# Sheet1.net
KiCad netlist of a schematic drawn in Altium Designer
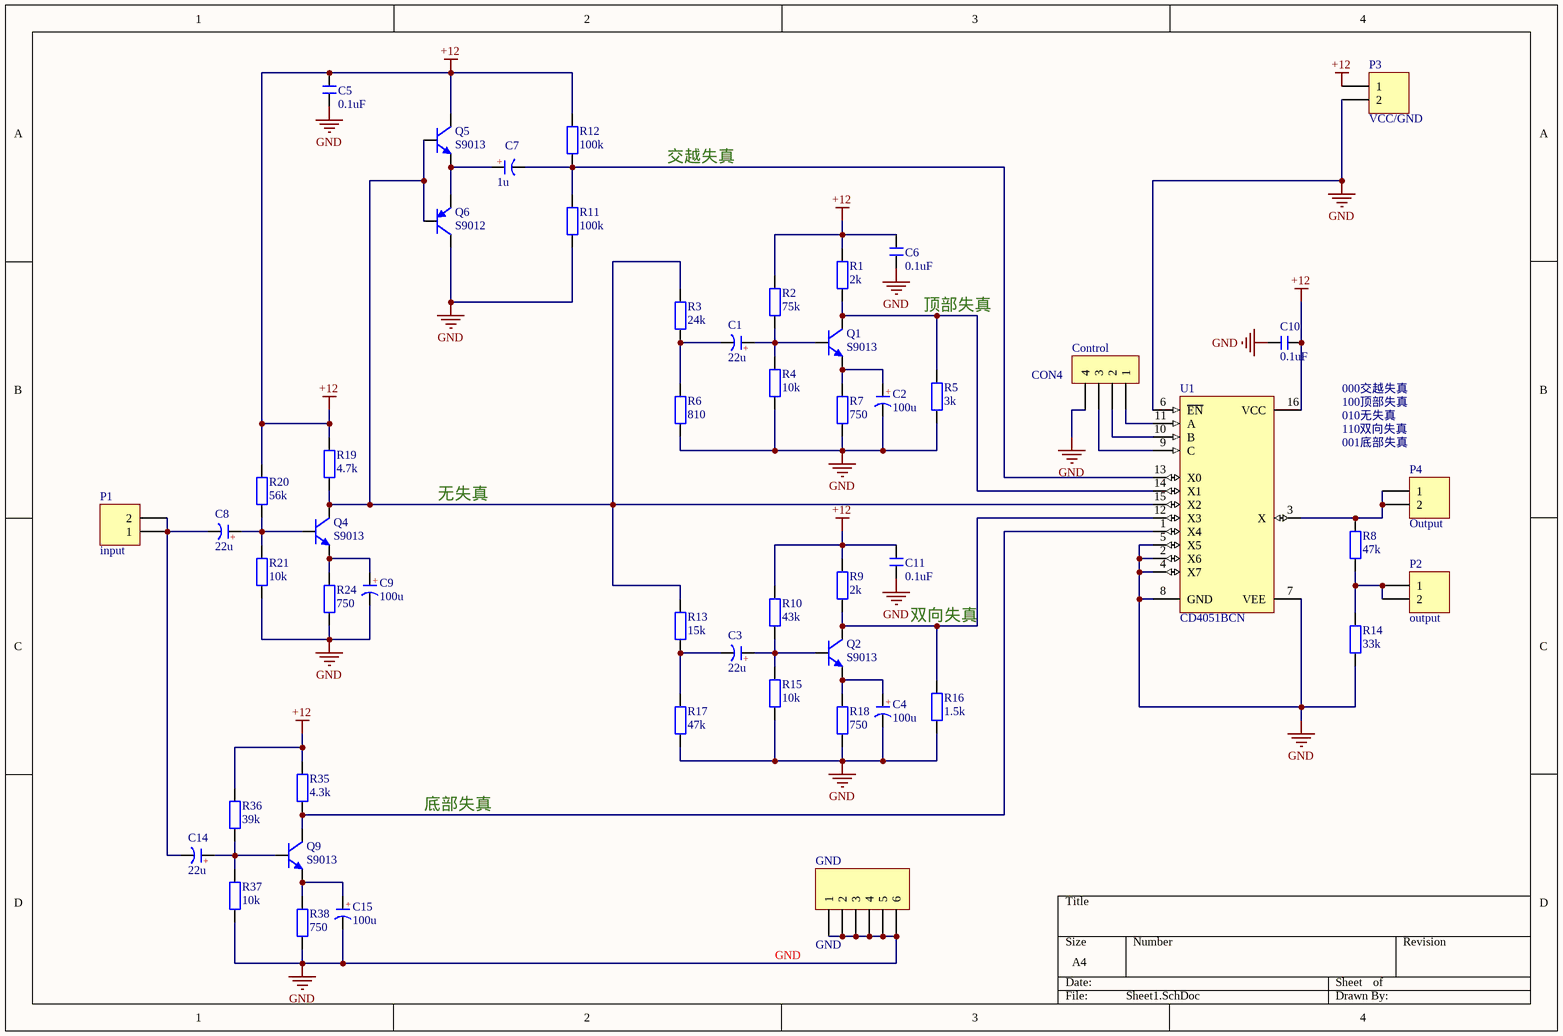
[diagram p0: Sheet1.SchDoc]

(export (version "E")
  (design (tool "Eeschema 10.0.6"))
  (components
    (comp (ref "C1")
      (value "22u")
      (footprint "CS 3.5*8*8 - R")
      (description "直插固态电容")
      (fields (field (name "版权归属") "源创客"))
      (libsource (lib "") (part "C-CS_1"))
    )
    (comp (ref "C2")
      (value "100u")
      (footprint "CS 3.5*8*8 - R")
      (description "直插固态电容")
      (fields (field (name "版权归属") "源创客"))
      (libsource (lib "3.1   - 电阻-电容-电感") (part "C-CS"))
    )
    (comp (ref "C3")
      (value "22u")
      (footprint "CS 3.5*8*8 - R")
      (description "直插固态电容")
      (fields (field (name "版权归属") "源创客"))
      (libsource (lib "") (part "C-CS_1"))
    )
    (comp (ref "C4")
      (value "100u")
      (footprint "CS 3.5*8*8 - R")
      (description "直插固态电容")
      (fields (field (name "版权归属") "源创客"))
      (libsource (lib "3.1   - 电阻-电容-电感") (part "C-CS"))
    )
    (comp (ref "C5")
      (value "0.1uF")
      (footprint "CBB-CL71")
      (description "CBB电容")
      (fields (field (name "版权归属") "源创客"))
      (libsource (lib "3.1   - 电阻-电容-电感") (part "C-CBB"))
    )
    (comp (ref "C6")
      (value "0.1uF")
      (footprint "CBB-CL71")
      (description "CBB电容")
      (fields (field (name "版权归属") "源创客"))
      (libsource (lib "3.1   - 电阻-电容-电感") (part "C-CBB"))
    )
    (comp (ref "C7")
      (value "1u")
      (footprint "CS 3.5*8*8 - R")
      (description "直插固态电容")
      (fields (field (name "版权归属") "源创客"))
      (libsource (lib "") (part "C-CS_1"))
    )
    (comp (ref "C8")
      (value "22u")
      (footprint "CS 3.5*8*8 - R")
      (description "直插固态电容")
      (fields (field (name "版权归属") "源创客"))
      (libsource (lib "") (part "C-CS_1"))
    )
    (comp (ref "C9")
      (value "100u")
      (footprint "CS 3.5*8*8 - R")
      (description "直插固态电容")
      (fields (field (name "版权归属") "源创客"))
      (libsource (lib "3.1   - 电阻-电容-电感") (part "C-CS"))
    )
    (comp (ref "C10")
      (value "0.1uF")
      (footprint "CBB-CL71")
      (description "CBB电容")
      (fields (field (name "版权归属") "源创客"))
      (libsource (lib "3.1   - 电阻-电容-电感") (part "C-CBB"))
    )
    (comp (ref "C11")
      (value "0.1uF")
      (footprint "CBB-CL71")
      (description "CBB电容")
      (fields (field (name "版权归属") "源创客"))
      (libsource (lib "3.1   - 电阻-电容-电感") (part "C-CBB"))
    )
    (comp (ref "C14")
      (value "22u")
      (footprint "CS 3.5*8*8 - R")
      (description "直插固态电容")
      (fields (field (name "版权归属") "源创客"))
      (libsource (lib "") (part "C-CS_1"))
    )
    (comp (ref "C15")
      (value "100u")
      (footprint "CS 3.5*8*8 - R")
      (description "直插固态电容")
      (fields (field (name "版权归属") "源创客"))
      (libsource (lib "3.1   - 电阻-电容-电感") (part "C-CS"))
    )
    (comp (ref "Control")
      (value "CON4")
      (footprint "HDR2.54-Y-LI-4P")
      (description "Connector")
      (libsource (lib "插件") (part "CON4"))
    )
    (comp (ref "GND")
      (value "GND")
      (footprint "HDR1X6")
      (description "Header, 6-Pin")
      (fields (field (name "PUBLISHER") "Altium Limited"))
      (libsource (lib "Miscellaneous Connectors") (part "Header 6"))
    )
    (comp (ref "P1")
      (value "input")
      (footprint "HDR1X2")
      (description "Header, 2-Pin")
      (fields (field (name "PUBLISHER") "Altium Limited"))
      (libsource (lib "Miscellaneous Connectors") (part "Header 2"))
    )
    (comp (ref "P2")
      (value "output")
      (footprint "HDR1X2")
      (description "Header, 2-Pin")
      (fields (field (name "PUBLISHER") "Altium Limited"))
      (libsource (lib "") (part "Header 2_1"))
    )
    (comp (ref "P3")
      (value "VCC/GND")
      (footprint "XH2.54-LI-2P")
      (description "Header, 2-Pin")
      (fields (field (name "PUBLISHER") "Altium Limited"))
      (libsource (lib "") (part "Header 2_1"))
    )
    (comp (ref "P4")
      (value "Output")
      (footprint "HDR1X2")
      (description "Header, 2-Pin")
      (fields (field (name "PUBLISHER") "Altium Limited"))
      (libsource (lib "") (part "Header 2_1"))
    )
    (comp (ref "Q1")
      (value "S9013")
      (footprint "TO92")
      (description "低频放大-NPN型")
      (fields (field (name "版权归属") "源创客"))
      (libsource (lib "6.2   - 三极管") (part "9013-DIP"))
    )
    (comp (ref "Q2")
      (value "S9013")
      (footprint "TO92")
      (description "低频放大-NPN型")
      (fields (field (name "版权归属") "源创客"))
      (libsource (lib "6.2   - 三极管") (part "9013-DIP"))
    )
    (comp (ref "Q4")
      (value "S9013")
      (footprint "TO92")
      (description "低频放大-NPN型")
      (fields (field (name "版权归属") "源创客"))
      (libsource (lib "6.2   - 三极管") (part "9013-DIP"))
    )
    (comp (ref "Q5")
      (value "S9013")
      (footprint "TO92")
      (description "低频放大-NPN型")
      (fields (field (name "版权归属") "源创客"))
      (libsource (lib "6.2   - 三极管") (part "9013-DIP"))
    )
    (comp (ref "Q6")
      (value "S9012")
      (footprint "TO92")
      (description "低频放大-PNP型")
      (fields (field (name "版权归属") "源创客"))
      (libsource (lib "6.2   - 三极管") (part "9012-DIP"))
    )
    (comp (ref "Q9")
      (value "S9013")
      (footprint "TO92")
      (description "低频放大-NPN型")
      (fields (field (name "版权归属") "源创客"))
      (libsource (lib "6.2   - 三极管") (part "9013-DIP"))
    )
    (comp (ref "R1")
      (value "2k")
      (footprint "RS 1/4W")
      (description "直插色环电阻")
      (fields (field (name "版权归属") "源创客"))
      (libsource (lib "3.1   - 电阻-电容-电感") (part "R-CRR"))
    )
    (comp (ref "R2")
      (value "75k")
      (footprint "RS 1/4W")
      (description "直插色环电阻")
      (fields (field (name "版权归属") "源创客"))
      (libsource (lib "3.1   - 电阻-电容-电感") (part "R-CRR"))
    )
    (comp (ref "R3")
      (value "24k")
      (footprint "RS 1/4W")
      (description "直插色环电阻")
      (fields (field (name "版权归属") "源创客"))
      (libsource (lib "3.1   - 电阻-电容-电感") (part "R-CRR"))
    )
    (comp (ref "R4")
      (value "10k")
      (footprint "RS 1/4W")
      (description "直插色环电阻")
      (fields (field (name "版权归属") "源创客"))
      (libsource (lib "3.1   - 电阻-电容-电感") (part "R-CRR"))
    )
    (comp (ref "R5")
      (value "3k")
      (footprint "RS 1/4W")
      (description "直插色环电阻")
      (fields (field (name "版权归属") "源创客"))
      (libsource (lib "3.1   - 电阻-电容-电感") (part "R-CRR"))
    )
    (comp (ref "R6")
      (value "810")
      (footprint "RS 1/4W")
      (description "直插色环电阻")
      (fields (field (name "版权归属") "源创客"))
      (libsource (lib "3.1   - 电阻-电容-电感") (part "R-CRR"))
    )
    (comp (ref "R7")
      (value "750")
      (footprint "RS 1/4W")
      (description "直插色环电阻")
      (fields (field (name "版权归属") "源创客"))
      (libsource (lib "3.1   - 电阻-电容-电感") (part "R-CRR"))
    )
    (comp (ref "R8")
      (value "47k")
      (footprint "RS 1/4W")
      (description "直插色环电阻")
      (fields (field (name "版权归属") "源创客"))
      (libsource (lib "3.1   - 电阻-电容-电感") (part "R-CRR"))
    )
    (comp (ref "R9")
      (value "2k")
      (footprint "RS 1/4W")
      (description "直插色环电阻")
      (fields (field (name "版权归属") "源创客"))
      (libsource (lib "3.1   - 电阻-电容-电感") (part "R-CRR"))
    )
    (comp (ref "R10")
      (value "43k")
      (footprint "RS 1/4W")
      (description "直插色环电阻")
      (fields (field (name "版权归属") "源创客"))
      (libsource (lib "3.1   - 电阻-电容-电感") (part "R-CRR"))
    )
    (comp (ref "R11")
      (value "100k")
      (footprint "RS 1/4W")
      (description "直插色环电阻")
      (fields (field (name "版权归属") "源创客"))
      (libsource (lib "3.1   - 电阻-电容-电感") (part "R-CRR"))
    )
    (comp (ref "R12")
      (value "100k")
      (footprint "RS 1/4W")
      (description "直插色环电阻")
      (fields (field (name "版权归属") "源创客"))
      (libsource (lib "3.1   - 电阻-电容-电感") (part "R-CRR"))
    )
    (comp (ref "R13")
      (value "15k")
      (footprint "RS 1/4W")
      (description "直插色环电阻")
      (fields (field (name "版权归属") "源创客"))
      (libsource (lib "3.1   - 电阻-电容-电感") (part "R-CRR"))
    )
    (comp (ref "R14")
      (value "33k")
      (footprint "RS 1/4W")
      (description "直插色环电阻")
      (fields (field (name "版权归属") "源创客"))
      (libsource (lib "3.1   - 电阻-电容-电感") (part "R-CRR"))
    )
    (comp (ref "R15")
      (value "10k")
      (footprint "RS 1/4W")
      (description "直插色环电阻")
      (fields (field (name "版权归属") "源创客"))
      (libsource (lib "3.1   - 电阻-电容-电感") (part "R-CRR"))
    )
    (comp (ref "R16")
      (value "1.5k")
      (footprint "RS 1/4W")
      (description "直插色环电阻")
      (fields (field (name "版权归属") "源创客"))
      (libsource (lib "3.1   - 电阻-电容-电感") (part "R-CRR"))
    )
    (comp (ref "R17")
      (value "47k")
      (footprint "RS 1/4W")
      (description "直插色环电阻")
      (fields (field (name "版权归属") "源创客"))
      (libsource (lib "3.1   - 电阻-电容-电感") (part "R-CRR"))
    )
    (comp (ref "R18")
      (value "750")
      (footprint "RS 1/4W")
      (description "直插色环电阻")
      (fields (field (name "版权归属") "源创客"))
      (libsource (lib "3.1   - 电阻-电容-电感") (part "R-CRR"))
    )
    (comp (ref "R19")
      (value "4.7k")
      (footprint "RS 1/4W")
      (description "直插色环电阻")
      (fields (field (name "版权归属") "源创客"))
      (libsource (lib "3.1   - 电阻-电容-电感") (part "R-CRR"))
    )
    (comp (ref "R20")
      (value "56k")
      (footprint "RS 1/4W")
      (description "直插色环电阻")
      (fields (field (name "版权归属") "源创客"))
      (libsource (lib "3.1   - 电阻-电容-电感") (part "R-CRR"))
    )
    (comp (ref "R21")
      (value "10k")
      (footprint "RS 1/4W")
      (description "直插色环电阻")
      (fields (field (name "版权归属") "源创客"))
      (libsource (lib "3.1   - 电阻-电容-电感") (part "R-CRR"))
    )
    (comp (ref "R24")
      (value "750")
      (footprint "RS 1/4W")
      (description "直插色环电阻")
      (fields (field (name "版权归属") "源创客"))
      (libsource (lib "3.1   - 电阻-电容-电感") (part "R-CRR"))
    )
    (comp (ref "R35")
      (value "4.3k")
      (footprint "RS 1/4W")
      (description "直插色环电阻")
      (fields (field (name "版权归属") "源创客"))
      (libsource (lib "3.1   - 电阻-电容-电感") (part "R-CRR"))
    )
    (comp (ref "R36")
      (value "39k")
      (footprint "RS 1/4W")
      (description "直插色环电阻")
      (fields (field (name "版权归属") "源创客"))
      (libsource (lib "3.1   - 电阻-电容-电感") (part "R-CRR"))
    )
    (comp (ref "R37")
      (value "10k")
      (footprint "RS 1/4W")
      (description "直插色环电阻")
      (fields (field (name "版权归属") "源创客"))
      (libsource (lib "3.1   - 电阻-电容-电感") (part "R-CRR"))
    )
    (comp (ref "R38")
      (value "750")
      (footprint "RS 1/4W")
      (description "直插色环电阻")
      (fields (field (name "版权归属") "源创客"))
      (libsource (lib "3.1   - 电阻-电容-电感") (part "R-CRR"))
    )
    (comp (ref "U1")
      (value "CD4051BCN")
      (footprint "N16E")
      (description "8-Channel Analog Multiplexer/Demultiplexer")
      (fields (field (name "PUBLISHER") "Altium Limited"))
      (libsource (lib "FSC Logic Multiplexer") (part "CD4051BCN"))
    )
  )
  (nets
    (net (code "1") (name "+12") (class "Default")
      (node (ref "C10") (pin "1") (pinfunction "1_1") (pintype "passive"))
      (node (ref "C11") (pin "1") (pinfunction "1_1") (pintype "passive"))
      (node (ref "C5") (pin "1") (pinfunction "1_1") (pintype "passive"))
      (node (ref "C6") (pin "1") (pinfunction "1_1") (pintype "passive"))
      (node (ref "P3") (pin "1") (pinfunction "1_1") (pintype "passive"))
      (node (ref "Q5") (pin "3") (pinfunction "C_3") (pintype "passive"))
      (node (ref "R1") (pin "2") (pinfunction "2_2") (pintype "passive"))
      (node (ref "R10") (pin "2") (pinfunction "2_2") (pintype "passive"))
      (node (ref "R12") (pin "2") (pinfunction "2_2") (pintype "passive"))
      (node (ref "R19") (pin "2") (pinfunction "2_2") (pintype "passive"))
      (node (ref "R2") (pin "2") (pinfunction "2_2") (pintype "passive"))
      (node (ref "R20") (pin "2") (pinfunction "2_2") (pintype "passive"))
      (node (ref "R35") (pin "2") (pinfunction "2_2") (pintype "passive"))
      (node (ref "R36") (pin "2") (pinfunction "2_2") (pintype "passive"))
      (node (ref "R9") (pin "2") (pinfunction "2_2") (pintype "passive"))
      (node (ref "U1") (pin "16") (pinfunction "VCC_16") (pintype "power_in"))
    )
    (net (code "2") (name "GND") (class "Default")
      (node (ref "C10") (pin "2") (pinfunction "2_2") (pintype "passive"))
      (node (ref "C11") (pin "2") (pinfunction "2_2") (pintype "passive"))
      (node (ref "C15") (pin "2") (pinfunction "K_2") (pintype "passive"))
      (node (ref "C2") (pin "2") (pinfunction "K_2") (pintype "passive"))
      (node (ref "C4") (pin "2") (pinfunction "K_2") (pintype "passive"))
      (node (ref "C5") (pin "2") (pinfunction "2_2") (pintype "passive"))
      (node (ref "C6") (pin "2") (pinfunction "2_2") (pintype "passive"))
      (node (ref "C9") (pin "2") (pinfunction "K_2") (pintype "passive"))
      (node (ref "Control") (pin "4") (pinfunction "4_4") (pintype "passive"))
      (node (ref "GND") (pin "1") (pinfunction "1_1") (pintype "passive"))
      (node (ref "GND") (pin "2") (pinfunction "2_2") (pintype "passive"))
      (node (ref "GND") (pin "3") (pinfunction "3_3") (pintype "passive"))
      (node (ref "GND") (pin "4") (pinfunction "4_4") (pintype "passive"))
      (node (ref "GND") (pin "5") (pinfunction "5_5") (pintype "passive"))
      (node (ref "GND") (pin "6") (pinfunction "6_6") (pintype "passive"))
      (node (ref "P3") (pin "2") (pinfunction "2_2") (pintype "passive"))
      (node (ref "Q6") (pin "3") (pinfunction "C_3") (pintype "passive"))
      (node (ref "R11") (pin "1") (pinfunction "1_1") (pintype "passive"))
      (node (ref "R14") (pin "1") (pinfunction "1_1") (pintype "passive"))
      (node (ref "R15") (pin "1") (pinfunction "1_1") (pintype "passive"))
      (node (ref "R16") (pin "1") (pinfunction "1_1") (pintype "passive"))
      (node (ref "R17") (pin "1") (pinfunction "1_1") (pintype "passive"))
      (node (ref "R18") (pin "1") (pinfunction "1_1") (pintype "passive"))
      (node (ref "R21") (pin "1") (pinfunction "1_1") (pintype "passive"))
      (node (ref "R24") (pin "1") (pinfunction "1_1") (pintype "passive"))
      (node (ref "R37") (pin "1") (pinfunction "1_1") (pintype "passive"))
      (node (ref "R38") (pin "1") (pinfunction "1_1") (pintype "passive"))
      (node (ref "R4") (pin "1") (pinfunction "1_1") (pintype "passive"))
      (node (ref "R5") (pin "1") (pinfunction "1_1") (pintype "passive"))
      (node (ref "R6") (pin "1") (pinfunction "1_1") (pintype "passive"))
      (node (ref "R7") (pin "1") (pinfunction "1_1") (pintype "passive"))
      (node (ref "U1") (pin "2") (pinfunction "X6_2") (pintype "bidirectional"))
      (node (ref "U1") (pin "4") (pinfunction "X7_4") (pintype "bidirectional"))
      (node (ref "U1") (pin "5") (pinfunction "X5_5") (pintype "bidirectional"))
      (node (ref "U1") (pin "6") (pinfunction "~{EN}_6") (pintype "input"))
      (node (ref "U1") (pin "7") (pinfunction "VEE_7") (pintype "power_in"))
      (node (ref "U1") (pin "8") (pinfunction "GND_8") (pintype "power_in"))
    )
    (net (code "3") (name "Net-(C1-A)") (class "Default")
      (node (ref "C1") (pin "1") (pinfunction "A_1") (pintype "passive"))
      (node (ref "Q1") (pin "2") (pinfunction "B_2") (pintype "passive"))
      (node (ref "R2") (pin "1") (pinfunction "1_1") (pintype "passive"))
      (node (ref "R4") (pin "2") (pinfunction "2_2") (pintype "passive"))
    )
    (net (code "4") (name "Net-(C1-K)") (class "Default")
      (node (ref "C1") (pin "2") (pinfunction "K_2") (pintype "passive"))
      (node (ref "R3") (pin "1") (pinfunction "1_1") (pintype "passive"))
      (node (ref "R6") (pin "2") (pinfunction "2_2") (pintype "passive"))
    )
    (net (code "5") (name "Net-(C2-A)") (class "Default")
      (node (ref "C2") (pin "1") (pinfunction "A_1") (pintype "passive"))
      (node (ref "Q1") (pin "1") (pinfunction "E_1") (pintype "passive"))
      (node (ref "R7") (pin "2") (pinfunction "2_2") (pintype "passive"))
    )
    (net (code "6") (name "Net-(C3-A)") (class "Default")
      (node (ref "C3") (pin "1") (pinfunction "A_1") (pintype "passive"))
      (node (ref "Q2") (pin "2") (pinfunction "B_2") (pintype "passive"))
      (node (ref "R10") (pin "1") (pinfunction "1_1") (pintype "passive"))
      (node (ref "R15") (pin "2") (pinfunction "2_2") (pintype "passive"))
    )
    (net (code "7") (name "Net-(C3-K)") (class "Default")
      (node (ref "C3") (pin "2") (pinfunction "K_2") (pintype "passive"))
      (node (ref "R13") (pin "1") (pinfunction "1_1") (pintype "passive"))
      (node (ref "R17") (pin "2") (pinfunction "2_2") (pintype "passive"))
    )
    (net (code "8") (name "Net-(C4-A)") (class "Default")
      (node (ref "C4") (pin "1") (pinfunction "A_1") (pintype "passive"))
      (node (ref "Q2") (pin "1") (pinfunction "E_1") (pintype "passive"))
      (node (ref "R18") (pin "2") (pinfunction "2_2") (pintype "passive"))
    )
    (net (code "9") (name "Net-(C7-A)") (class "Default")
      (node (ref "C7") (pin "1") (pinfunction "A_1") (pintype "passive"))
      (node (ref "Q5") (pin "1") (pinfunction "E_1") (pintype "passive"))
      (node (ref "Q6") (pin "1") (pinfunction "E_1") (pintype "passive"))
    )
    (net (code "10") (name "Net-(C7-K)") (class "Default")
      (node (ref "C7") (pin "2") (pinfunction "K_2") (pintype "passive"))
      (node (ref "R11") (pin "2") (pinfunction "2_2") (pintype "passive"))
      (node (ref "R12") (pin "1") (pinfunction "1_1") (pintype "passive"))
      (node (ref "U1") (pin "13") (pinfunction "X0_13") (pintype "bidirectional"))
    )
    (net (code "11") (name "Net-(C8-A)") (class "Default")
      (node (ref "C8") (pin "1") (pinfunction "A_1") (pintype "passive"))
      (node (ref "Q4") (pin "2") (pinfunction "B_2") (pintype "passive"))
      (node (ref "R20") (pin "1") (pinfunction "1_1") (pintype "passive"))
      (node (ref "R21") (pin "2") (pinfunction "2_2") (pintype "passive"))
    )
    (net (code "12") (name "Net-(C9-A)") (class "Default")
      (node (ref "C9") (pin "1") (pinfunction "A_1") (pintype "passive"))
      (node (ref "Q4") (pin "1") (pinfunction "E_1") (pintype "passive"))
      (node (ref "R24") (pin "2") (pinfunction "2_2") (pintype "passive"))
    )
    (net (code "13") (name "Net-(C14-A)") (class "Default")
      (node (ref "C14") (pin "1") (pinfunction "A_1") (pintype "passive"))
      (node (ref "Q9") (pin "2") (pinfunction "B_2") (pintype "passive"))
      (node (ref "R36") (pin "1") (pinfunction "1_1") (pintype "passive"))
      (node (ref "R37") (pin "2") (pinfunction "2_2") (pintype "passive"))
    )
    (net (code "14") (name "Net-(C14-K)") (class "Default")
      (node (ref "C14") (pin "2") (pinfunction "K_2") (pintype "passive"))
      (node (ref "C8") (pin "2") (pinfunction "K_2") (pintype "passive"))
      (node (ref "P1") (pin "1") (pinfunction "1_1") (pintype "passive"))
      (node (ref "P1") (pin "2") (pinfunction "2_2") (pintype "passive"))
    )
    (net (code "15") (name "Net-(C15-A)") (class "Default")
      (node (ref "C15") (pin "1") (pinfunction "A_1") (pintype "passive"))
      (node (ref "Q9") (pin "1") (pinfunction "E_1") (pintype "passive"))
      (node (ref "R38") (pin "2") (pinfunction "2_2") (pintype "passive"))
    )
    (net (code "16") (name "Net-(P2-Pad1)") (class "Default")
      (node (ref "P2") (pin "1") (pinfunction "1_1") (pintype "passive"))
      (node (ref "P2") (pin "2") (pinfunction "2_2") (pintype "passive"))
      (node (ref "R14") (pin "2") (pinfunction "2_2") (pintype "passive"))
      (node (ref "R8") (pin "1") (pinfunction "1_1") (pintype "passive"))
    )
    (net (code "17") (name "Net-(Q1-C)") (class "Default")
      (node (ref "Q1") (pin "3") (pinfunction "C_3") (pintype "passive"))
      (node (ref "R1") (pin "1") (pinfunction "1_1") (pintype "passive"))
      (node (ref "R5") (pin "2") (pinfunction "2_2") (pintype "passive"))
      (node (ref "U1") (pin "14") (pinfunction "X1_14") (pintype "bidirectional"))
    )
    (net (code "18") (name "Net-(Q2-C)") (class "Default")
      (node (ref "Q2") (pin "3") (pinfunction "C_3") (pintype "passive"))
      (node (ref "R16") (pin "2") (pinfunction "2_2") (pintype "passive"))
      (node (ref "R9") (pin "1") (pinfunction "1_1") (pintype "passive"))
      (node (ref "U1") (pin "12") (pinfunction "X3_12") (pintype "bidirectional"))
    )
    (net (code "19") (name "Net-(Q4-C)") (class "Default")
      (node (ref "Q4") (pin "3") (pinfunction "C_3") (pintype "passive"))
      (node (ref "Q5") (pin "2") (pinfunction "B_2") (pintype "passive"))
      (node (ref "Q6") (pin "2") (pinfunction "B_2") (pintype "passive"))
      (node (ref "R13") (pin "2") (pinfunction "2_2") (pintype "passive"))
      (node (ref "R19") (pin "1") (pinfunction "1_1") (pintype "passive"))
      (node (ref "R3") (pin "2") (pinfunction "2_2") (pintype "passive"))
      (node (ref "U1") (pin "15") (pinfunction "X2_15") (pintype "bidirectional"))
    )
    (net (code "20") (name "Net-(Q9-C)") (class "Default")
      (node (ref "Q9") (pin "3") (pinfunction "C_3") (pintype "passive"))
      (node (ref "R35") (pin "1") (pinfunction "1_1") (pintype "passive"))
      (node (ref "U1") (pin "1") (pinfunction "X4_1") (pintype "bidirectional"))
    )
    (net (code "21") (name "Net-(U1-A)") (class "Default")
      (node (ref "Control") (pin "1") (pinfunction "1_1") (pintype "passive"))
      (node (ref "U1") (pin "11") (pinfunction "A_11") (pintype "input"))
    )
    (net (code "22") (name "Net-(U1-B)") (class "Default")
      (node (ref "Control") (pin "2") (pinfunction "2_2") (pintype "passive"))
      (node (ref "U1") (pin "10") (pinfunction "B_10") (pintype "input"))
    )
    (net (code "23") (name "Net-(U1-C)") (class "Default")
      (node (ref "Control") (pin "3") (pinfunction "3_3") (pintype "passive"))
      (node (ref "U1") (pin "9") (pinfunction "C_9") (pintype "input"))
    )
    (net (code "24") (name "Net-(U1-X)") (class "Default")
      (node (ref "P4") (pin "1") (pinfunction "1_1") (pintype "passive"))
      (node (ref "P4") (pin "2") (pinfunction "2_2") (pintype "passive"))
      (node (ref "R8") (pin "2") (pinfunction "2_2") (pintype "passive"))
      (node (ref "U1") (pin "3") (pinfunction "X_3") (pintype "bidirectional"))
    )
  )
)
